# MCU02.net
KiCad netlist of a schematic drawn in Altium Designer
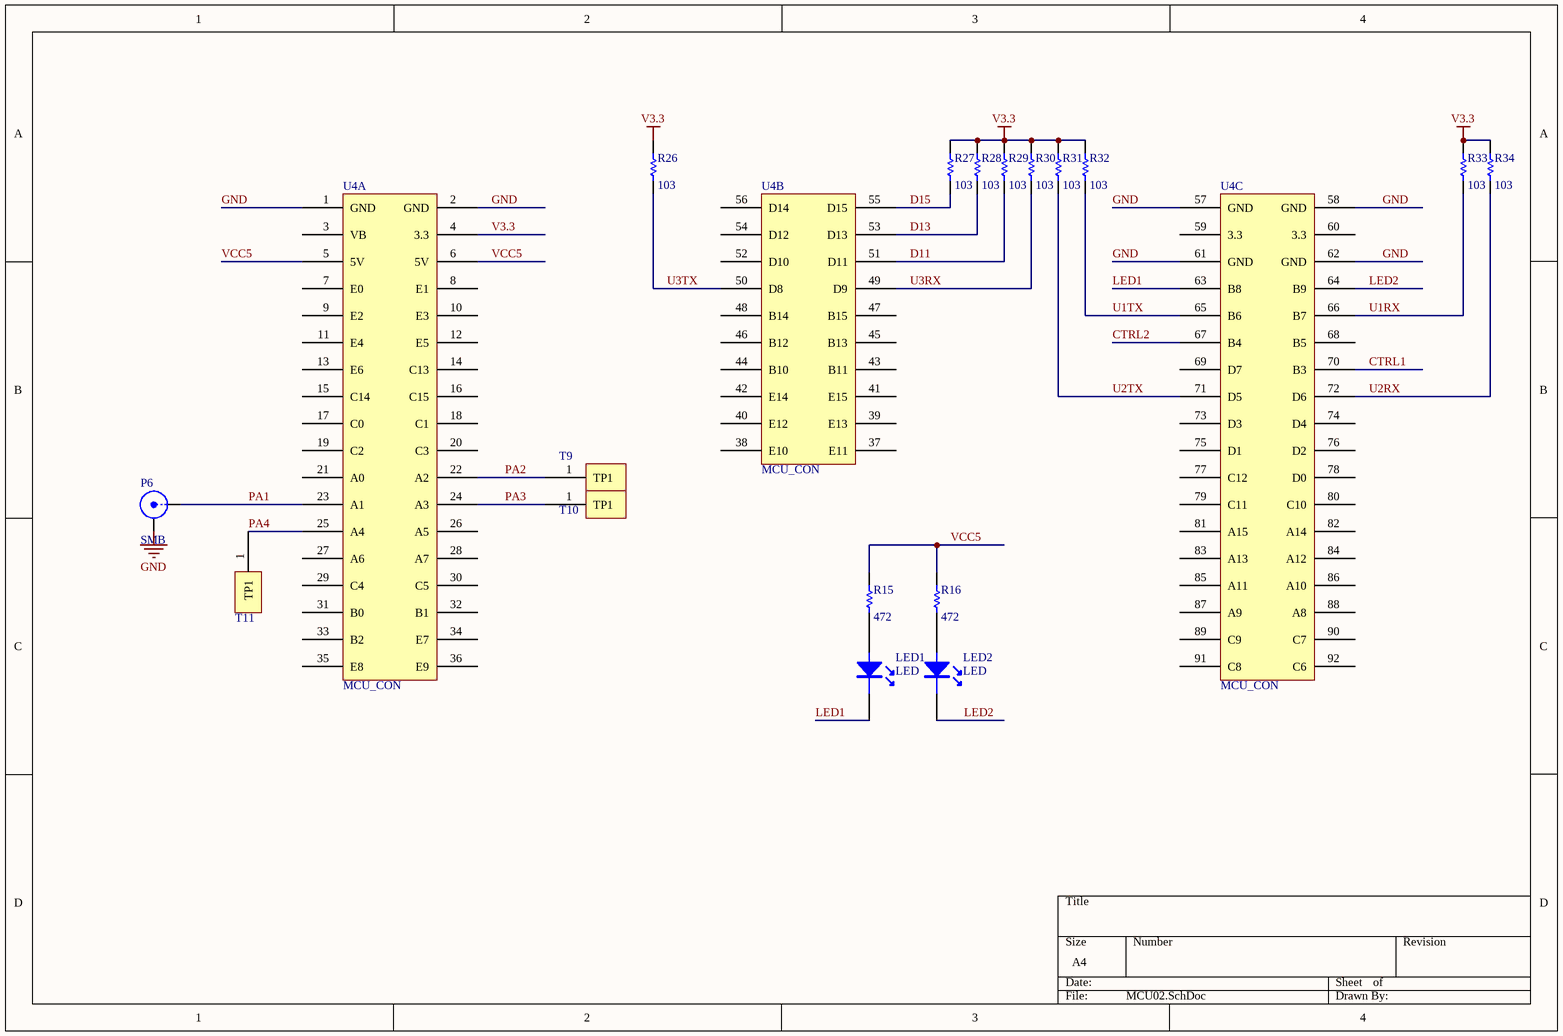
[diagram p0: MCU02.SchDoc]

(export (version "E")
  (design (tool "Eeschema 10.0.6"))
  (components
    (comp (ref "LED1") (value "LED") (footprint "0805_LED") (libsource (lib "Schlib1") (part "LED")))
    (comp (ref "LED2") (value "LED") (footprint "0805_LED") (libsource (lib "Schlib1") (part "LED")))
    (comp (ref "P6")
      (value "SMB")
      (footprint "SMB_V-RJ45")
      (description "SMB Straight Connector")
      (fields (field (name "PUBLISHER") "Altium Limited"))
      (libsource (lib "Miscellaneous Connectors") (part "SMB"))
    )
    (comp (ref "R15")
      (value "472")
      (footprint "1206")
      (description "Semiconductor Resistor")
      (fields (field (name "Comment") "Res Semi") (field (name "PUBLISHER") "Altium Limited"))
      (libsource (lib "Miscellaneous Devices") (part "Res Semi"))
    )
    (comp (ref "R16")
      (value "472")
      (footprint "1206")
      (description "Semiconductor Resistor")
      (fields (field (name "Comment") "Res Semi") (field (name "PUBLISHER") "Altium Limited"))
      (libsource (lib "Miscellaneous Devices") (part "Res Semi"))
    )
    (comp (ref "R26")
      (value "103")
      (footprint "1206")
      (description "Semiconductor Resistor")
      (fields (field (name "Comment") "Res Semi") (field (name "PUBLISHER") "Altium Limited"))
      (libsource (lib "Miscellaneous Devices") (part "Res Semi"))
    )
    (comp (ref "R27")
      (value "103")
      (footprint "1206")
      (description "Semiconductor Resistor")
      (fields (field (name "Comment") "Res Semi") (field (name "PUBLISHER") "Altium Limited"))
      (libsource (lib "Miscellaneous Devices") (part "Res Semi"))
    )
    (comp (ref "R28")
      (value "103")
      (footprint "1206")
      (description "Semiconductor Resistor")
      (fields (field (name "Comment") "Res Semi") (field (name "PUBLISHER") "Altium Limited"))
      (libsource (lib "Miscellaneous Devices") (part "Res Semi"))
    )
    (comp (ref "R29")
      (value "103")
      (footprint "1206")
      (description "Semiconductor Resistor")
      (fields (field (name "Comment") "Res Semi") (field (name "PUBLISHER") "Altium Limited"))
      (libsource (lib "Miscellaneous Devices") (part "Res Semi"))
    )
    (comp (ref "R30")
      (value "103")
      (footprint "1206")
      (description "Semiconductor Resistor")
      (fields (field (name "Comment") "Res Semi") (field (name "PUBLISHER") "Altium Limited"))
      (libsource (lib "Miscellaneous Devices") (part "Res Semi"))
    )
    (comp (ref "R31")
      (value "103")
      (footprint "1206")
      (description "Semiconductor Resistor")
      (fields (field (name "Comment") "Res Semi") (field (name "PUBLISHER") "Altium Limited"))
      (libsource (lib "Miscellaneous Devices") (part "Res Semi"))
    )
    (comp (ref "R32")
      (value "103")
      (footprint "1206")
      (description "Semiconductor Resistor")
      (fields (field (name "Comment") "Res Semi") (field (name "PUBLISHER") "Altium Limited"))
      (libsource (lib "Miscellaneous Devices") (part "Res Semi"))
    )
    (comp (ref "R33")
      (value "103")
      (footprint "1206")
      (description "Semiconductor Resistor")
      (fields (field (name "Comment") "Res Semi") (field (name "PUBLISHER") "Altium Limited"))
      (libsource (lib "Miscellaneous Devices") (part "Res Semi"))
    )
    (comp (ref "R34")
      (value "103")
      (footprint "1206")
      (description "Semiconductor Resistor")
      (fields (field (name "Comment") "Res Semi") (field (name "PUBLISHER") "Altium Limited"))
      (libsource (lib "Miscellaneous Devices") (part "Res Semi"))
    )
    (comp (ref "T9") (value "TP1") (footprint "TP1") (libsource (lib "") (part "TP1_1")))
    (comp (ref "T10") (value "TP1") (footprint "TP1") (libsource (lib "") (part "TP1_1")))
    (comp (ref "T11") (value "TP1") (footprint "TP1") (libsource (lib "CHK-I") (part "TP1")))
    (comp (ref "U4") (value "MCU_CON") (footprint "MCU_CON") (libsource (lib "Schlib1") (part "MCU_CON")))
  )
  (nets
    (net (code "1") (name "/CTRL1") (class "Default")
      (node (ref "U4") (pin "70") (pinfunction "B3_70") (pintype "passive"))
    )
    (net (code "2") (name "/CTRL2") (class "Default")
      (node (ref "U4") (pin "67") (pinfunction "B4_67") (pintype "passive"))
    )
    (net (code "3") (name "/D11") (class "Default")
      (node (ref "R29") (pin "1") (pinfunction "1_1") (pintype "passive"))
      (node (ref "U4") (pin "51") (pinfunction "D11_51") (pintype "passive"))
    )
    (net (code "4") (name "/D13") (class "Default")
      (node (ref "R28") (pin "1") (pinfunction "1_1") (pintype "passive"))
      (node (ref "U4") (pin "53") (pinfunction "D13_53") (pintype "passive"))
    )
    (net (code "5") (name "/D15") (class "Default")
      (node (ref "R27") (pin "1") (pinfunction "1_1") (pintype "passive"))
      (node (ref "U4") (pin "55") (pinfunction "D15_55") (pintype "passive"))
    )
    (net (code "6") (name "/LED1") (class "Default")
      (node (ref "LED1") (pin "2") (pinfunction "K_2") (pintype "passive"))
      (node (ref "U4") (pin "63") (pinfunction "B8_63") (pintype "passive"))
    )
    (net (code "7") (name "/LED2") (class "Default")
      (node (ref "LED2") (pin "2") (pinfunction "K_2") (pintype "passive"))
      (node (ref "U4") (pin "64") (pinfunction "B9_64") (pintype "passive"))
    )
    (net (code "8") (name "/PA1") (class "Default")
      (node (ref "P6") (pin "1") (pinfunction "X_1") (pintype "passive"))
      (node (ref "U4") (pin "23") (pinfunction "A1_23") (pintype "passive"))
    )
    (net (code "9") (name "/PA2") (class "Default")
      (node (ref "T9") (pin "1") (pinfunction "TP1_1") (pintype "passive"))
      (node (ref "U4") (pin "22") (pinfunction "A2_22") (pintype "passive"))
    )
    (net (code "10") (name "/PA3") (class "Default")
      (node (ref "T10") (pin "1") (pinfunction "TP1_1") (pintype "passive"))
      (node (ref "U4") (pin "24") (pinfunction "A3_24") (pintype "passive"))
    )
    (net (code "11") (name "/PA4") (class "Default")
      (node (ref "T11") (pin "1") (pinfunction "TP1_1") (pintype "passive"))
      (node (ref "U4") (pin "25") (pinfunction "A4_25") (pintype "passive"))
    )
    (net (code "12") (name "/U1RX") (class "Default")
      (node (ref "R33") (pin "1") (pinfunction "1_1") (pintype "passive"))
      (node (ref "U4") (pin "66") (pinfunction "B7_66") (pintype "passive"))
    )
    (net (code "13") (name "/U1TX") (class "Default")
      (node (ref "R32") (pin "1") (pinfunction "1_1") (pintype "passive"))
      (node (ref "U4") (pin "65") (pinfunction "B6_65") (pintype "passive"))
    )
    (net (code "14") (name "/U2RX") (class "Default")
      (node (ref "R34") (pin "1") (pinfunction "1_1") (pintype "passive"))
      (node (ref "U4") (pin "72") (pinfunction "D6_72") (pintype "passive"))
    )
    (net (code "15") (name "/U2TX") (class "Default")
      (node (ref "R31") (pin "1") (pinfunction "1_1") (pintype "passive"))
      (node (ref "U4") (pin "71") (pinfunction "D5_71") (pintype "passive"))
    )
    (net (code "16") (name "/U3RX") (class "Default")
      (node (ref "R30") (pin "1") (pinfunction "1_1") (pintype "passive"))
      (node (ref "U4") (pin "49") (pinfunction "D9_49") (pintype "passive"))
    )
    (net (code "17") (name "/U3TX") (class "Default")
      (node (ref "R26") (pin "1") (pinfunction "1_1") (pintype "passive"))
      (node (ref "U4") (pin "50") (pinfunction "D8_50") (pintype "passive"))
    )
    (net (code "18") (name "/VCC5") (class "Default")
      (node (ref "R15") (pin "2") (pinfunction "2_2") (pintype "passive"))
      (node (ref "R16") (pin "2") (pinfunction "2_2") (pintype "passive"))
      (node (ref "U4") (pin "5") (pinfunction "5V_5") (pintype "passive"))
      (node (ref "U4") (pin "6") (pinfunction "5V_6") (pintype "passive"))
    )
    (net (code "19") (name "GND") (class "Default")
      (node (ref "P6") (pin "2") (pinfunction "Y_2") (pintype "passive"))
      (node (ref "U4") (pin "1") (pinfunction "GND_1") (pintype "passive"))
      (node (ref "U4") (pin "2") (pinfunction "GND_2") (pintype "passive"))
      (node (ref "U4") (pin "57") (pinfunction "GND_57") (pintype "passive"))
      (node (ref "U4") (pin "58") (pinfunction "GND_58") (pintype "passive"))
      (node (ref "U4") (pin "61") (pinfunction "GND_61") (pintype "passive"))
      (node (ref "U4") (pin "62") (pinfunction "GND_62") (pintype "passive"))
    )
    (net (code "20") (name "Net-(LED1-A)") (class "Default")
      (node (ref "LED1") (pin "1") (pinfunction "A_1") (pintype "passive"))
      (node (ref "R15") (pin "1") (pinfunction "1_1") (pintype "passive"))
    )
    (net (code "21") (name "Net-(LED2-A)") (class "Default")
      (node (ref "LED2") (pin "1") (pinfunction "A_1") (pintype "passive"))
      (node (ref "R16") (pin "1") (pinfunction "1_1") (pintype "passive"))
    )
    (net (code "22") (name "V3.3") (class "Default")
      (node (ref "R26") (pin "2") (pinfunction "2_2") (pintype "passive"))
      (node (ref "R27") (pin "2") (pinfunction "2_2") (pintype "passive"))
      (node (ref "R28") (pin "2") (pinfunction "2_2") (pintype "passive"))
      (node (ref "R29") (pin "2") (pinfunction "2_2") (pintype "passive"))
      (node (ref "R30") (pin "2") (pinfunction "2_2") (pintype "passive"))
      (node (ref "R31") (pin "2") (pinfunction "2_2") (pintype "passive"))
      (node (ref "R32") (pin "2") (pinfunction "2_2") (pintype "passive"))
      (node (ref "R33") (pin "2") (pinfunction "2_2") (pintype "passive"))
      (node (ref "R34") (pin "2") (pinfunction "2_2") (pintype "passive"))
      (node (ref "U4") (pin "4") (pinfunction "3.3_4") (pintype "passive"))
    )
    (net (code "23") (name "unconnected-(U4A-A0-Pad21)") (class "Default")
      (node (ref "U4") (pin "21") (pinfunction "A0_21") (pintype "passive"))
    )
    (net (code "24") (name "unconnected-(U4A-A5-Pad26)") (class "Default")
      (node (ref "U4") (pin "26") (pinfunction "A5_26") (pintype "passive"))
    )
    (net (code "25") (name "unconnected-(U4A-A6-Pad27)") (class "Default")
      (node (ref "U4") (pin "27") (pinfunction "A6_27") (pintype "passive"))
    )
    (net (code "26") (name "unconnected-(U4A-A7-Pad28)") (class "Default")
      (node (ref "U4") (pin "28") (pinfunction "A7_28") (pintype "passive"))
    )
    (net (code "27") (name "unconnected-(U4A-B0-Pad31)") (class "Default")
      (node (ref "U4") (pin "31") (pinfunction "B0_31") (pintype "passive"))
    )
    (net (code "28") (name "unconnected-(U4A-B1-Pad32)") (class "Default")
      (node (ref "U4") (pin "32") (pinfunction "B1_32") (pintype "passive"))
    )
    (net (code "29") (name "unconnected-(U4A-B2-Pad33)") (class "Default")
      (node (ref "U4") (pin "33") (pinfunction "B2_33") (pintype "passive"))
    )
    (net (code "30") (name "unconnected-(U4A-C0-Pad17)") (class "Default")
      (node (ref "U4") (pin "17") (pinfunction "C0_17") (pintype "passive"))
    )
    (net (code "31") (name "unconnected-(U4A-C1-Pad18)") (class "Default")
      (node (ref "U4") (pin "18") (pinfunction "C1_18") (pintype "passive"))
    )
    (net (code "32") (name "unconnected-(U4A-C2-Pad19)") (class "Default")
      (node (ref "U4") (pin "19") (pinfunction "C2_19") (pintype "passive"))
    )
    (net (code "33") (name "unconnected-(U4A-C3-Pad20)") (class "Default")
      (node (ref "U4") (pin "20") (pinfunction "C3_20") (pintype "passive"))
    )
    (net (code "34") (name "unconnected-(U4A-C4-Pad29)") (class "Default")
      (node (ref "U4") (pin "29") (pinfunction "C4_29") (pintype "passive"))
    )
    (net (code "35") (name "unconnected-(U4A-C5-Pad30)") (class "Default")
      (node (ref "U4") (pin "30") (pinfunction "C5_30") (pintype "passive"))
    )
    (net (code "36") (name "unconnected-(U4A-C13-Pad14)") (class "Default")
      (node (ref "U4") (pin "14") (pinfunction "C13_14") (pintype "passive"))
    )
    (net (code "37") (name "unconnected-(U4A-C14-Pad15)") (class "Default")
      (node (ref "U4") (pin "15") (pinfunction "C14_15") (pintype "passive"))
    )
    (net (code "38") (name "unconnected-(U4A-C15-Pad16)") (class "Default")
      (node (ref "U4") (pin "16") (pinfunction "C15_16") (pintype "passive"))
    )
    (net (code "39") (name "unconnected-(U4A-E0-Pad7)") (class "Default")
      (node (ref "U4") (pin "7") (pinfunction "E0_7") (pintype "passive"))
    )
    (net (code "40") (name "unconnected-(U4A-E1-Pad8)") (class "Default")
      (node (ref "U4") (pin "8") (pinfunction "E1_8") (pintype "passive"))
    )
    (net (code "41") (name "unconnected-(U4A-E2-Pad9)") (class "Default")
      (node (ref "U4") (pin "9") (pinfunction "E2_9") (pintype "passive"))
    )
    (net (code "42") (name "unconnected-(U4A-E3-Pad10)") (class "Default")
      (node (ref "U4") (pin "10") (pinfunction "E3_10") (pintype "passive"))
    )
    (net (code "43") (name "unconnected-(U4A-E4-Pad11)") (class "Default")
      (node (ref "U4") (pin "11") (pinfunction "E4_11") (pintype "passive"))
    )
    (net (code "44") (name "unconnected-(U4A-E5-Pad12)") (class "Default")
      (node (ref "U4") (pin "12") (pinfunction "E5_12") (pintype "passive"))
    )
    (net (code "45") (name "unconnected-(U4A-E6-Pad13)") (class "Default")
      (node (ref "U4") (pin "13") (pinfunction "E6_13") (pintype "passive"))
    )
    (net (code "46") (name "unconnected-(U4A-E7-Pad34)") (class "Default")
      (node (ref "U4") (pin "34") (pinfunction "E7_34") (pintype "passive"))
    )
    (net (code "47") (name "unconnected-(U4A-E8-Pad35)") (class "Default")
      (node (ref "U4") (pin "35") (pinfunction "E8_35") (pintype "passive"))
    )
    (net (code "48") (name "unconnected-(U4A-E9-Pad36)") (class "Default")
      (node (ref "U4") (pin "36") (pinfunction "E9_36") (pintype "passive"))
    )
    (net (code "49") (name "unconnected-(U4A-VB-Pad3)") (class "Default")
      (node (ref "U4") (pin "3") (pinfunction "VB_3") (pintype "passive"))
    )
    (net (code "50") (name "unconnected-(U4B-B10-Pad44)") (class "Default")
      (node (ref "U4") (pin "44") (pinfunction "B10_44") (pintype "passive"))
    )
    (net (code "51") (name "unconnected-(U4B-B11-Pad43)") (class "Default")
      (node (ref "U4") (pin "43") (pinfunction "B11_43") (pintype "passive"))
    )
    (net (code "52") (name "unconnected-(U4B-B12-Pad46)") (class "Default")
      (node (ref "U4") (pin "46") (pinfunction "B12_46") (pintype "passive"))
    )
    (net (code "53") (name "unconnected-(U4B-B13-Pad45)") (class "Default")
      (node (ref "U4") (pin "45") (pinfunction "B13_45") (pintype "passive"))
    )
    (net (code "54") (name "unconnected-(U4B-B14-Pad48)") (class "Default")
      (node (ref "U4") (pin "48") (pinfunction "B14_48") (pintype "passive"))
    )
    (net (code "55") (name "unconnected-(U4B-B15-Pad47)") (class "Default")
      (node (ref "U4") (pin "47") (pinfunction "B15_47") (pintype "passive"))
    )
    (net (code "56") (name "unconnected-(U4B-D10-Pad52)") (class "Default")
      (node (ref "U4") (pin "52") (pinfunction "D10_52") (pintype "passive"))
    )
    (net (code "57") (name "unconnected-(U4B-D12-Pad54)") (class "Default")
      (node (ref "U4") (pin "54") (pinfunction "D12_54") (pintype "passive"))
    )
    (net (code "58") (name "unconnected-(U4B-D14-Pad56)") (class "Default")
      (node (ref "U4") (pin "56") (pinfunction "D14_56") (pintype "passive"))
    )
    (net (code "59") (name "unconnected-(U4B-E10-Pad38)") (class "Default")
      (node (ref "U4") (pin "38") (pinfunction "E10_38") (pintype "passive"))
    )
    (net (code "60") (name "unconnected-(U4B-E11-Pad37)") (class "Default")
      (node (ref "U4") (pin "37") (pinfunction "E11_37") (pintype "passive"))
    )
    (net (code "61") (name "unconnected-(U4B-E12-Pad40)") (class "Default")
      (node (ref "U4") (pin "40") (pinfunction "E12_40") (pintype "passive"))
    )
    (net (code "62") (name "unconnected-(U4B-E13-Pad39)") (class "Default")
      (node (ref "U4") (pin "39") (pinfunction "E13_39") (pintype "passive"))
    )
    (net (code "63") (name "unconnected-(U4B-E14-Pad42)") (class "Default")
      (node (ref "U4") (pin "42") (pinfunction "E14_42") (pintype "passive"))
    )
    (net (code "64") (name "unconnected-(U4B-E15-Pad41)") (class "Default")
      (node (ref "U4") (pin "41") (pinfunction "E15_41") (pintype "passive"))
    )
    (net (code "65") (name "unconnected-(U4C-3.3-Pad59)") (class "Default")
      (node (ref "U4") (pin "59") (pinfunction "3.3_59") (pintype "passive"))
    )
    (net (code "66") (name "unconnected-(U4C-3.3-Pad60)") (class "Default")
      (node (ref "U4") (pin "60") (pinfunction "3.3_60") (pintype "passive"))
    )
    (net (code "67") (name "unconnected-(U4C-A8-Pad88)") (class "Default")
      (node (ref "U4") (pin "88") (pinfunction "A8_88") (pintype "passive"))
    )
    (net (code "68") (name "unconnected-(U4C-A9-Pad87)") (class "Default")
      (node (ref "U4") (pin "87") (pinfunction "A9_87") (pintype "passive"))
    )
    (net (code "69") (name "unconnected-(U4C-A10-Pad86)") (class "Default")
      (node (ref "U4") (pin "86") (pinfunction "A10_86") (pintype "passive"))
    )
    (net (code "70") (name "unconnected-(U4C-A11-Pad85)") (class "Default")
      (node (ref "U4") (pin "85") (pinfunction "A11_85") (pintype "passive"))
    )
    (net (code "71") (name "unconnected-(U4C-A12-Pad84)") (class "Default")
      (node (ref "U4") (pin "84") (pinfunction "A12_84") (pintype "passive"))
    )
    (net (code "72") (name "unconnected-(U4C-A13-Pad83)") (class "Default")
      (node (ref "U4") (pin "83") (pinfunction "A13_83") (pintype "passive"))
    )
    (net (code "73") (name "unconnected-(U4C-A14-Pad82)") (class "Default")
      (node (ref "U4") (pin "82") (pinfunction "A14_82") (pintype "passive"))
    )
    (net (code "74") (name "unconnected-(U4C-A15-Pad81)") (class "Default")
      (node (ref "U4") (pin "81") (pinfunction "A15_81") (pintype "passive"))
    )
    (net (code "75") (name "unconnected-(U4C-B5-Pad68)") (class "Default")
      (node (ref "U4") (pin "68") (pinfunction "B5_68") (pintype "passive"))
    )
    (net (code "76") (name "unconnected-(U4C-C6-Pad92)") (class "Default")
      (node (ref "U4") (pin "92") (pinfunction "C6_92") (pintype "passive"))
    )
    (net (code "77") (name "unconnected-(U4C-C7-Pad90)") (class "Default")
      (node (ref "U4") (pin "90") (pinfunction "C7_90") (pintype "passive"))
    )
    (net (code "78") (name "unconnected-(U4C-C8-Pad91)") (class "Default")
      (node (ref "U4") (pin "91") (pinfunction "C8_91") (pintype "passive"))
    )
    (net (code "79") (name "unconnected-(U4C-C9-Pad89)") (class "Default")
      (node (ref "U4") (pin "89") (pinfunction "C9_89") (pintype "passive"))
    )
    (net (code "80") (name "unconnected-(U4C-C10-Pad80)") (class "Default")
      (node (ref "U4") (pin "80") (pinfunction "C10_80") (pintype "passive"))
    )
    (net (code "81") (name "unconnected-(U4C-C11-Pad79)") (class "Default")
      (node (ref "U4") (pin "79") (pinfunction "C11_79") (pintype "passive"))
    )
    (net (code "82") (name "unconnected-(U4C-C12-Pad77)") (class "Default")
      (node (ref "U4") (pin "77") (pinfunction "C12_77") (pintype "passive"))
    )
    (net (code "83") (name "unconnected-(U4C-D0-Pad78)") (class "Default")
      (node (ref "U4") (pin "78") (pinfunction "D0_78") (pintype "passive"))
    )
    (net (code "84") (name "unconnected-(U4C-D1-Pad75)") (class "Default")
      (node (ref "U4") (pin "75") (pinfunction "D1_75") (pintype "passive"))
    )
    (net (code "85") (name "unconnected-(U4C-D2-Pad76)") (class "Default")
      (node (ref "U4") (pin "76") (pinfunction "D2_76") (pintype "passive"))
    )
    (net (code "86") (name "unconnected-(U4C-D3-Pad73)") (class "Default")
      (node (ref "U4") (pin "73") (pinfunction "D3_73") (pintype "passive"))
    )
    (net (code "87") (name "unconnected-(U4C-D4-Pad74)") (class "Default")
      (node (ref "U4") (pin "74") (pinfunction "D4_74") (pintype "passive"))
    )
    (net (code "88") (name "unconnected-(U4C-D7-Pad69)") (class "Default")
      (node (ref "U4") (pin "69") (pinfunction "D7_69") (pintype "passive"))
    )
  )
)
